# Z-Axis_Stepper_Motor_Driver.net
KiCad netlist of a schematic drawn in Altium Designer
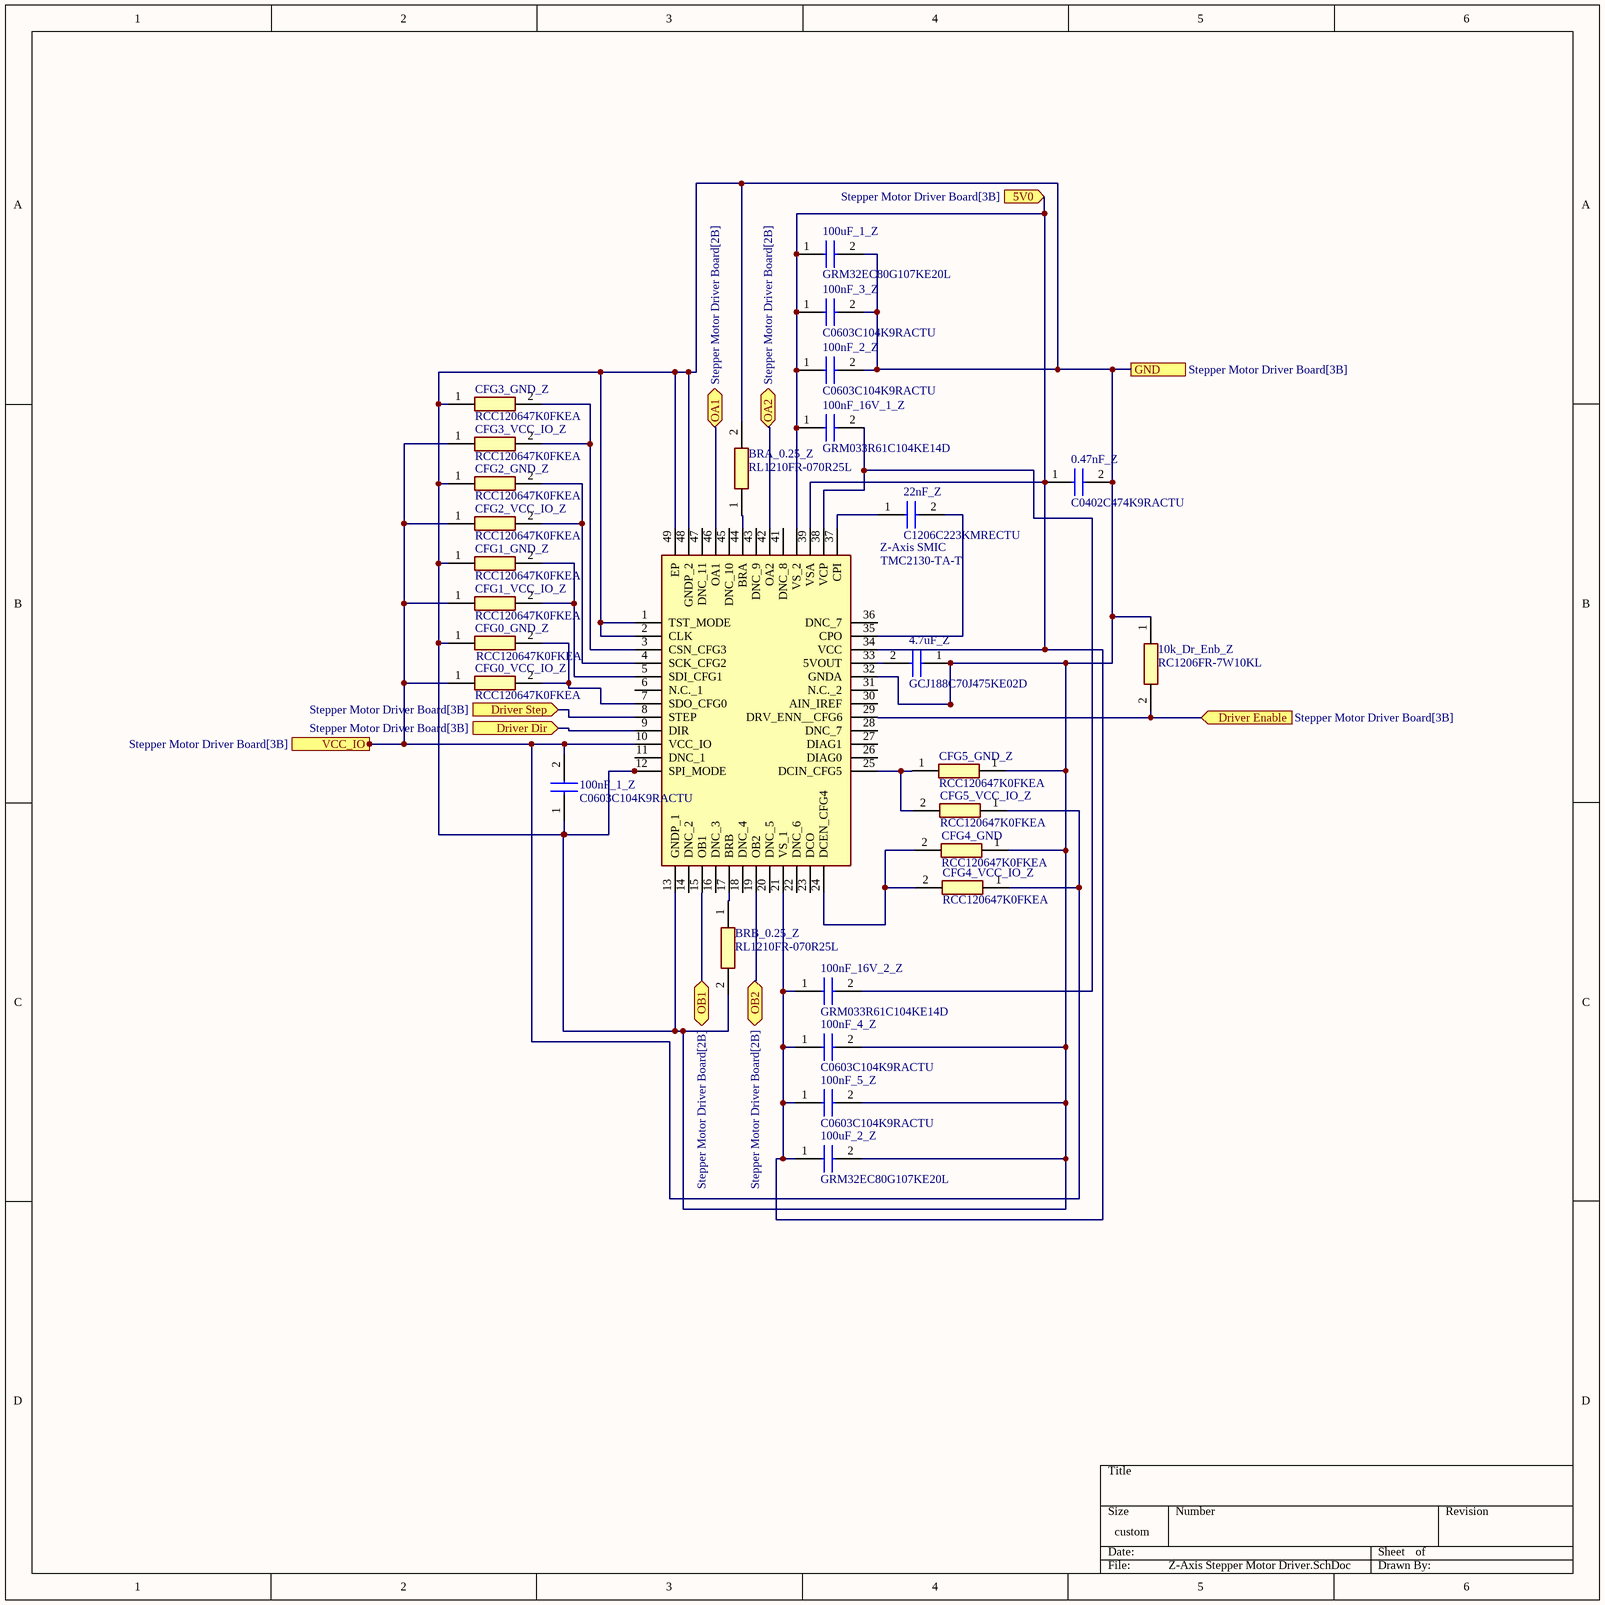
[diagram p0: Z-Axis Stepper Motor Driver.SchDoc]

(export (version "E")
  (design (tool "Eeschema 10.0.6"))
  (components
    (comp (ref "0.47nF_Z")
      (value "C0402C474K9RACTU")
      (footprint "SamacSys:CAPC1005X55N")
      (description "Capacitor")
      (fields (field (name "MOUSER PART NUMBER") "80-C0402C474K9RACTU"))
      (libsource (lib "*") (part "C0402C474K9RACTU"))
    )
    (comp (ref "4.7uF_Z")
      (value "GCJ188C70J475KE02D")
      (footprint "SamacSys:CAPC1608X100N")
      (description "Capacitor")
      (fields (field (name "MOUSER PART NUMBER") "81-GCJ188C70J475KE2D"))
      (libsource (lib "*") (part "GCJ188C70J475KE02D"))
    )
    (comp (ref "10k_Dr_Enb_Z")
      (value "RC1206FR-7W10KL")
      (footprint "SamacSys:RESC3116X65N")
      (description "Resistor")
      (libsource (lib "*") (part "RC1206FR-7W10KL"))
    )
    (comp (ref "22nF_Z")
      (value "C1206C223KMRECTU")
      (footprint "SamacSys:C1206")
      (description "Capacitor")
      (fields (field (name "MOUSER PART NUMBER") "80-C1206C223KMRECTU"))
      (libsource (lib "*") (part "C1206C223KMRECTU"))
    )
    (comp (ref "100nF_1_Z")
      (value "C0603C104K9RACTU")
      (footprint "SamacSys:C0603")
      (description "Capacitor")
      (fields (field (name "MOUSER PART NUMBER") "80-C0603C104K9R"))
      (libsource (lib "*") (part "C0603C104K9RACTU"))
    )
    (comp (ref "100nF_2_Z")
      (value "C0603C104K9RACTU")
      (footprint "SamacSys:C0603")
      (description "Capacitor")
      (fields (field (name "MOUSER PART NUMBER") "80-C0603C104K9R"))
      (libsource (lib "*") (part "C0603C104K9RACTU"))
    )
    (comp (ref "100nF_3_Z")
      (value "C0603C104K9RACTU")
      (footprint "SamacSys:C0603")
      (description "Capacitor")
      (fields (field (name "MOUSER PART NUMBER") "80-C0603C104K9R"))
      (libsource (lib "*") (part "C0603C104K9RACTU"))
    )
    (comp (ref "100nF_4_Z")
      (value "C0603C104K9RACTU")
      (footprint "SamacSys:C0603")
      (description "Capacitor")
      (fields (field (name "MOUSER PART NUMBER") "80-C0603C104K9R"))
      (libsource (lib "*") (part "C0603C104K9RACTU"))
    )
    (comp (ref "100nF_5_Z")
      (value "C0603C104K9RACTU")
      (footprint "SamacSys:C0603")
      (description "Capacitor")
      (fields (field (name "MOUSER PART NUMBER") "80-C0603C104K9R"))
      (libsource (lib "*") (part "C0603C104K9RACTU"))
    )
    (comp (ref "100nF_16V_1_Z")
      (value "GRM033R61C104KE14D")
      (footprint "SamacSys:CAPC0603X33N")
      (description "Capacitor")
      (fields (field (name "MOUSER PART NUMBER") "81-GRM033R61C104KE4D"))
      (libsource (lib "*") (part "GRM033R61C104KE14D"))
    )
    (comp (ref "100nF_16V_2_Z")
      (value "GRM033R61C104KE14D")
      (footprint "SamacSys:CAPC0603X33N")
      (description "Capacitor")
      (fields (field (name "MOUSER PART NUMBER") "81-GRM033R61C104KE4D"))
      (libsource (lib "*") (part "GRM033R61C104KE14D"))
    )
    (comp (ref "100uF_1_Z")
      (value "GRM32EC80G107KE20L")
      (footprint "SamacSys:CAPC3225X270N")
      (description "Capacitor")
      (fields (field (name "MOUSER PART NUMBER") "81-GRM32EC80G107KE0L"))
      (libsource (lib "*") (part "GRM32EC80G107KE20L"))
    )
    (comp (ref "100uF_2_Z")
      (value "GRM32EC80G107KE20L")
      (footprint "SamacSys:CAPC3225X270N")
      (description "Capacitor")
      (fields (field (name "MOUSER PART NUMBER") "81-GRM32EC80G107KE0L"))
      (libsource (lib "*") (part "GRM32EC80G107KE20L"))
    )
    (comp (ref "BRA_0.25_Z")
      (value "RL1210FR-070R25L")
      (footprint "SamacSys:RESC3126X65N")
      (description "Resistor")
      (fields (field (name "MOUSER PART NUMBER") "603-RL1210FR-070R25L"))
      (libsource (lib "") (part "RL1210FR-070R25L_1"))
    )
    (comp (ref "BRB_0.25_Z")
      (value "RL1210FR-070R25L")
      (footprint "SamacSys:RESC3126X65N")
      (description "Resistor")
      (fields (field (name "MOUSER PART NUMBER") "603-RL1210FR-070R25L"))
      (libsource (lib "*") (part "RL1210FR-070R25L"))
    )
    (comp (ref "CFG0_GND_Z")
      (value "RCC120647K0FKEA")
      (footprint "SamacSys:RCC1206_e3")
      (description "Resistor")
      (fields (field (name "MOUSER PART NUMBER") "71-RCC120647K0FKEA"))
      (libsource (lib "") (part "RCC120647K0FKEA_1"))
    )
    (comp (ref "CFG0_VCC_IO_Z")
      (value "RCC120647K0FKEA")
      (footprint "SamacSys:RCC1206_e3")
      (description "Resistor")
      (fields (field (name "MOUSER PART NUMBER") "71-RCC120647K0FKEA"))
      (libsource (lib "") (part "RCC120647K0FKEA_1"))
    )
    (comp (ref "CFG1_GND_Z")
      (value "RCC120647K0FKEA")
      (footprint "SamacSys:RCC1206_e3")
      (description "Resistor")
      (fields (field (name "MOUSER PART NUMBER") "71-RCC120647K0FKEA"))
      (libsource (lib "") (part "RCC120647K0FKEA_1"))
    )
    (comp (ref "CFG1_VCC_IO_Z")
      (value "RCC120647K0FKEA")
      (footprint "SamacSys:RCC1206_e3")
      (description "Resistor")
      (fields (field (name "MOUSER PART NUMBER") "71-RCC120647K0FKEA"))
      (libsource (lib "") (part "RCC120647K0FKEA_1"))
    )
    (comp (ref "CFG2_GND_Z")
      (value "RCC120647K0FKEA")
      (footprint "SamacSys:RCC1206_e3")
      (description "Resistor")
      (fields (field (name "MOUSER PART NUMBER") "71-RCC120647K0FKEA"))
      (libsource (lib "") (part "RCC120647K0FKEA_1"))
    )
    (comp (ref "CFG2_VCC_IO_Z")
      (value "RCC120647K0FKEA")
      (footprint "SamacSys:RCC1206_e3")
      (description "Resistor")
      (fields (field (name "MOUSER PART NUMBER") "71-RCC120647K0FKEA"))
      (libsource (lib "") (part "RCC120647K0FKEA_1"))
    )
    (comp (ref "CFG3_GND_Z")
      (value "RCC120647K0FKEA")
      (footprint "SamacSys:RCC1206_e3")
      (description "Resistor")
      (fields (field (name "MOUSER PART NUMBER") "71-RCC120647K0FKEA"))
      (libsource (lib "") (part "RCC120647K0FKEA_1"))
    )
    (comp (ref "CFG3_VCC_IO_Z")
      (value "RCC120647K0FKEA")
      (footprint "SamacSys:RCC1206_e3")
      (description "Resistor")
      (fields (field (name "MOUSER PART NUMBER") "71-RCC120647K0FKEA"))
      (libsource (lib "") (part "RCC120647K0FKEA_1"))
    )
    (comp (ref "CFG4_GND")
      (value "RCC120647K0FKEA")
      (footprint "SamacSys:RCC1206_e3")
      (description "Resistor")
      (fields (field (name "MOUSER PART NUMBER") "71-RCC120647K0FKEA"))
      (libsource (lib "*") (part "RCC120647K0FKEA"))
    )
    (comp (ref "CFG4_VCC_IO_Z")
      (value "RCC120647K0FKEA")
      (footprint "SamacSys:RCC1206_e3")
      (description "Resistor")
      (fields (field (name "MOUSER PART NUMBER") "71-RCC120647K0FKEA"))
      (libsource (lib "*") (part "RCC120647K0FKEA"))
    )
    (comp (ref "CFG5_GND_Z")
      (value "RCC120647K0FKEA")
      (footprint "SamacSys:RCC1206_e3")
      (description "Resistor")
      (fields (field (name "MOUSER PART NUMBER") "71-RCC120647K0FKEA"))
      (libsource (lib "") (part "RCC120647K0FKEA_2"))
    )
    (comp (ref "CFG5_VCC_IO_Z")
      (value "RCC120647K0FKEA")
      (footprint "SamacSys:RCC1206_e3")
      (description "Resistor")
      (fields (field (name "MOUSER PART NUMBER") "71-RCC120647K0FKEA"))
      (libsource (lib "*") (part "RCC120647K0FKEA"))
    )
    (comp (ref "Z-Axis SMIC")
      (value "TMC2130-TA-T")
      (footprint "SamacSys:QFP50P900X900X120-49N")
      (description "Integrated Circuit")
      (fields (field (name "MOUSER PART NUMBER") "700-TMC2130-TA-T"))
      (libsource (lib "*") (part "TMC2130-TA-T"))
    )
  )
  (nets
    (net (code "1") (name "/5V0") (class "Default")
      (node (ref "0.47nF_Z") (pin "1") (pinfunction "1_1") (pintype "passive"))
      (node (ref "100nF_16V_1_Z") (pin "1") (pinfunction "1_1") (pintype "passive"))
      (node (ref "100nF_16V_2_Z") (pin "1") (pinfunction "1_1") (pintype "passive"))
      (node (ref "100nF_2_Z") (pin "1") (pinfunction "1_1") (pintype "passive"))
      (node (ref "100nF_3_Z") (pin "1") (pinfunction "1_1") (pintype "passive"))
      (node (ref "100nF_4_Z") (pin "1") (pinfunction "1_1") (pintype "passive"))
      (node (ref "100nF_5_Z") (pin "1") (pinfunction "1_1") (pintype "passive"))
      (node (ref "100uF_1_Z") (pin "1") (pinfunction "1_1") (pintype "passive"))
      (node (ref "100uF_2_Z") (pin "1") (pinfunction "1_1") (pintype "passive"))
      (node (ref "Z-Axis SMIC") (pin "21") (pinfunction "VS_1_21") (pintype "passive"))
      (node (ref "Z-Axis SMIC") (pin "34") (pinfunction "VCC_34") (pintype "passive"))
      (node (ref "Z-Axis SMIC") (pin "39") (pinfunction "VSA_39") (pintype "passive"))
      (node (ref "Z-Axis SMIC") (pin "40") (pinfunction "VS_2_40") (pintype "passive"))
    )
    (net (code "2") (name "/Driver Dir") (class "Default")
      (node (ref "Z-Axis SMIC") (pin "9") (pinfunction "DIR_9") (pintype "passive"))
    )
    (net (code "3") (name "/Driver Enable") (class "Default")
      (node (ref "10k_Dr_Enb_Z") (pin "2") (pinfunction "2_2") (pintype "passive"))
      (node (ref "Z-Axis SMIC") (pin "29") (pinfunction "DRV_ENN__CFG6_29") (pintype "passive"))
    )
    (net (code "4") (name "/Driver Step") (class "Default")
      (node (ref "Z-Axis SMIC") (pin "8") (pinfunction "STEP_8") (pintype "passive"))
    )
    (net (code "5") (name "/GND") (class "Default")
      (node (ref "0.47nF_Z") (pin "2") (pinfunction "2_2") (pintype "passive"))
      (node (ref "100nF_1_Z") (pin "1") (pinfunction "1_1") (pintype "passive"))
      (node (ref "100nF_2_Z") (pin "2") (pinfunction "2_2") (pintype "passive"))
      (node (ref "100nF_3_Z") (pin "2") (pinfunction "2_2") (pintype "passive"))
      (node (ref "100nF_4_Z") (pin "2") (pinfunction "2_2") (pintype "passive"))
      (node (ref "100nF_5_Z") (pin "2") (pinfunction "2_2") (pintype "passive"))
      (node (ref "100uF_1_Z") (pin "2") (pinfunction "2_2") (pintype "passive"))
      (node (ref "100uF_2_Z") (pin "2") (pinfunction "2_2") (pintype "passive"))
      (node (ref "10k_Dr_Enb_Z") (pin "1") (pinfunction "1_1") (pintype "passive"))
      (node (ref "4.7uF_Z") (pin "1") (pinfunction "1_1") (pintype "passive"))
      (node (ref "BRA_0.25_Z") (pin "2") (pinfunction "2_2") (pintype "passive"))
      (node (ref "BRB_0.25_Z") (pin "2") (pinfunction "2_2") (pintype "passive"))
      (node (ref "CFG0_GND_Z") (pin "1") (pinfunction "1_1") (pintype "passive"))
      (node (ref "CFG1_GND_Z") (pin "1") (pinfunction "1_1") (pintype "passive"))
      (node (ref "CFG2_GND_Z") (pin "1") (pinfunction "1_1") (pintype "passive"))
      (node (ref "CFG3_GND_Z") (pin "1") (pinfunction "1_1") (pintype "passive"))
      (node (ref "CFG4_GND") (pin "1") (pinfunction "1_1") (pintype "passive"))
      (node (ref "CFG5_GND_Z") (pin "1") (pinfunction "1_1") (pintype "passive"))
      (node (ref "Z-Axis SMIC") (pin "1") (pinfunction "TST_MODE_1") (pintype "passive"))
      (node (ref "Z-Axis SMIC") (pin "12") (pinfunction "SPI_MODE_12") (pintype "passive"))
      (node (ref "Z-Axis SMIC") (pin "13") (pinfunction "GNDP_1_13") (pintype "passive"))
      (node (ref "Z-Axis SMIC") (pin "2") (pinfunction "CLK_2") (pintype "passive"))
      (node (ref "Z-Axis SMIC") (pin "32") (pinfunction "GNDA_32") (pintype "passive"))
      (node (ref "Z-Axis SMIC") (pin "48") (pinfunction "GNDP_2_48") (pintype "passive"))
      (node (ref "Z-Axis SMIC") (pin "49") (pinfunction "EP_49") (pintype "passive"))
    )
    (net (code "6") (name "/OA1") (class "Default")
      (node (ref "Z-Axis SMIC") (pin "46") (pinfunction "OA1_46") (pintype "passive"))
    )
    (net (code "7") (name "/OA2") (class "Default")
      (node (ref "Z-Axis SMIC") (pin "42") (pinfunction "OA2_42") (pintype "passive"))
    )
    (net (code "8") (name "/OB1") (class "Default")
      (node (ref "Z-Axis SMIC") (pin "15") (pinfunction "OB1_15") (pintype "passive"))
    )
    (net (code "9") (name "/OB2") (class "Default")
      (node (ref "Z-Axis SMIC") (pin "19") (pinfunction "OB2_19") (pintype "passive"))
    )
    (net (code "10") (name "/VCC_IO") (class "Default")
      (node (ref "100nF_1_Z") (pin "2") (pinfunction "2_2") (pintype "passive"))
      (node (ref "CFG0_VCC_IO_Z") (pin "1") (pinfunction "1_1") (pintype "passive"))
      (node (ref "CFG1_VCC_IO_Z") (pin "1") (pinfunction "1_1") (pintype "passive"))
      (node (ref "CFG2_VCC_IO_Z") (pin "1") (pinfunction "1_1") (pintype "passive"))
      (node (ref "CFG3_VCC_IO_Z") (pin "1") (pinfunction "1_1") (pintype "passive"))
      (node (ref "CFG4_VCC_IO_Z") (pin "1") (pinfunction "1_1") (pintype "passive"))
      (node (ref "CFG5_VCC_IO_Z") (pin "1") (pinfunction "1_1") (pintype "passive"))
      (node (ref "Z-Axis SMIC") (pin "10") (pinfunction "VCC_IO_10") (pintype "passive"))
    )
    (net (code "11") (name "Net-(Z-Axis SMIC-5VOUT)") (class "Default")
      (node (ref "4.7uF_Z") (pin "2") (pinfunction "2_2") (pintype "passive"))
      (node (ref "Z-Axis SMIC") (pin "33") (pinfunction "5VOUT_33") (pintype "passive"))
    )
    (net (code "12") (name "Net-(Z-Axis SMIC-BRA)") (class "Default")
      (node (ref "BRA_0.25_Z") (pin "1") (pinfunction "1_1") (pintype "passive"))
      (node (ref "Z-Axis SMIC") (pin "44") (pinfunction "BRA_44") (pintype "passive"))
    )
    (net (code "13") (name "Net-(Z-Axis SMIC-BRB)") (class "Default")
      (node (ref "BRB_0.25_Z") (pin "1") (pinfunction "1_1") (pintype "passive"))
      (node (ref "Z-Axis SMIC") (pin "17") (pinfunction "BRB_17") (pintype "passive"))
    )
    (net (code "14") (name "Net-(Z-Axis SMIC-CPI)") (class "Default")
      (node (ref "22nF_Z") (pin "1") (pinfunction "1_1") (pintype "passive"))
      (node (ref "Z-Axis SMIC") (pin "37") (pinfunction "CPI_37") (pintype "passive"))
    )
    (net (code "15") (name "Net-(Z-Axis SMIC-CPO)") (class "Default")
      (node (ref "22nF_Z") (pin "2") (pinfunction "2_2") (pintype "passive"))
      (node (ref "Z-Axis SMIC") (pin "35") (pinfunction "CPO_35") (pintype "passive"))
    )
    (net (code "16") (name "Net-(Z-Axis SMIC-CSN_CFG3)") (class "Default")
      (node (ref "CFG3_GND_Z") (pin "2") (pinfunction "2_2") (pintype "passive"))
      (node (ref "CFG3_VCC_IO_Z") (pin "2") (pinfunction "2_2") (pintype "passive"))
      (node (ref "Z-Axis SMIC") (pin "3") (pinfunction "CSN_CFG3_3") (pintype "passive"))
    )
    (net (code "17") (name "Net-(Z-Axis SMIC-DCEN_CFG4)") (class "Default")
      (node (ref "CFG4_GND") (pin "2") (pinfunction "2_2") (pintype "passive"))
      (node (ref "CFG4_VCC_IO_Z") (pin "2") (pinfunction "2_2") (pintype "passive"))
      (node (ref "Z-Axis SMIC") (pin "24") (pinfunction "DCEN_CFG4_24") (pintype "passive"))
    )
    (net (code "18") (name "Net-(Z-Axis SMIC-DCIN_CFG5)") (class "Default")
      (node (ref "CFG5_GND_Z") (pin "1") (pinfunction "1_1") (pintype "passive"))
      (node (ref "CFG5_VCC_IO_Z") (pin "2") (pinfunction "2_2") (pintype "passive"))
      (node (ref "Z-Axis SMIC") (pin "25") (pinfunction "DCIN_CFG5_25") (pintype "passive"))
    )
    (net (code "19") (name "Net-(Z-Axis SMIC-SCK_CFG2)") (class "Default")
      (node (ref "CFG2_GND_Z") (pin "2") (pinfunction "2_2") (pintype "passive"))
      (node (ref "CFG2_VCC_IO_Z") (pin "2") (pinfunction "2_2") (pintype "passive"))
      (node (ref "Z-Axis SMIC") (pin "4") (pinfunction "SCK_CFG2_4") (pintype "passive"))
    )
    (net (code "20") (name "Net-(Z-Axis SMIC-SDI_CFG1)") (class "Default")
      (node (ref "CFG1_GND_Z") (pin "2") (pinfunction "2_2") (pintype "passive"))
      (node (ref "CFG1_VCC_IO_Z") (pin "2") (pinfunction "2_2") (pintype "passive"))
      (node (ref "Z-Axis SMIC") (pin "5") (pinfunction "SDI_CFG1_5") (pintype "passive"))
    )
    (net (code "21") (name "Net-(Z-Axis SMIC-SDO_CFG0)") (class "Default")
      (node (ref "CFG0_GND_Z") (pin "2") (pinfunction "2_2") (pintype "passive"))
      (node (ref "CFG0_VCC_IO_Z") (pin "2") (pinfunction "2_2") (pintype "passive"))
      (node (ref "Z-Axis SMIC") (pin "7") (pinfunction "SDO_CFG0_7") (pintype "passive"))
    )
    (net (code "22") (name "Net-(Z-Axis SMIC-VCP)") (class "Default")
      (node (ref "100nF_16V_1_Z") (pin "2") (pinfunction "2_2") (pintype "passive"))
      (node (ref "100nF_16V_2_Z") (pin "2") (pinfunction "2_2") (pintype "passive"))
      (node (ref "Z-Axis SMIC") (pin "38") (pinfunction "VCP_38") (pintype "passive"))
    )
    (net (code "23") (name "unconnected-(Z-Axis SMIC-AIN_IREF-Pad30)") (class "Default")
      (node (ref "Z-Axis SMIC") (pin "30") (pinfunction "AIN_IREF_30") (pintype "passive"))
    )
    (net (code "24") (name "unconnected-(Z-Axis SMIC-DCO-Pad23)") (class "Default")
      (node (ref "Z-Axis SMIC") (pin "23") (pinfunction "DCO_23") (pintype "passive"))
    )
    (net (code "25") (name "unconnected-(Z-Axis SMIC-DIAG0-Pad26)") (class "Default")
      (node (ref "Z-Axis SMIC") (pin "26") (pinfunction "DIAG0_26") (pintype "passive"))
    )
    (net (code "26") (name "unconnected-(Z-Axis SMIC-DIAG1-Pad27)") (class "Default")
      (node (ref "Z-Axis SMIC") (pin "27") (pinfunction "DIAG1_27") (pintype "passive"))
    )
    (net (code "27") (name "unconnected-(Z-Axis SMIC-DNC_1-Pad11)") (class "Default")
      (node (ref "Z-Axis SMIC") (pin "11") (pinfunction "DNC_1_11") (pintype "passive"))
    )
    (net (code "28") (name "unconnected-(Z-Axis SMIC-DNC_2-Pad14)") (class "Default")
      (node (ref "Z-Axis SMIC") (pin "14") (pinfunction "DNC_2_14") (pintype "passive"))
    )
    (net (code "29") (name "unconnected-(Z-Axis SMIC-DNC_3-Pad16)") (class "Default")
      (node (ref "Z-Axis SMIC") (pin "16") (pinfunction "DNC_3_16") (pintype "passive"))
    )
    (net (code "30") (name "unconnected-(Z-Axis SMIC-DNC_4-Pad18)") (class "Default")
      (node (ref "Z-Axis SMIC") (pin "18") (pinfunction "DNC_4_18") (pintype "passive"))
    )
    (net (code "31") (name "unconnected-(Z-Axis SMIC-DNC_5-Pad20)") (class "Default")
      (node (ref "Z-Axis SMIC") (pin "20") (pinfunction "DNC_5_20") (pintype "passive"))
    )
    (net (code "32") (name "unconnected-(Z-Axis SMIC-DNC_6-Pad22)") (class "Default")
      (node (ref "Z-Axis SMIC") (pin "22") (pinfunction "DNC_6_22") (pintype "passive"))
    )
    (net (code "33") (name "unconnected-(Z-Axis SMIC-DNC_7-Pad28)") (class "Default")
      (node (ref "Z-Axis SMIC") (pin "28") (pinfunction "DNC_7_28") (pintype "passive"))
    )
    (net (code "34") (name "unconnected-(Z-Axis SMIC-DNC_7-Pad36)") (class "Default")
      (node (ref "Z-Axis SMIC") (pin "36") (pinfunction "DNC_7_36") (pintype "passive"))
    )
    (net (code "35") (name "unconnected-(Z-Axis SMIC-DNC_8-Pad41)") (class "Default")
      (node (ref "Z-Axis SMIC") (pin "41") (pinfunction "DNC_8_41") (pintype "passive"))
    )
    (net (code "36") (name "unconnected-(Z-Axis SMIC-DNC_9-Pad43)") (class "Default")
      (node (ref "Z-Axis SMIC") (pin "43") (pinfunction "DNC_9_43") (pintype "passive"))
    )
    (net (code "37") (name "unconnected-(Z-Axis SMIC-DNC_10-Pad45)") (class "Default")
      (node (ref "Z-Axis SMIC") (pin "45") (pinfunction "DNC_10_45") (pintype "passive"))
    )
    (net (code "38") (name "unconnected-(Z-Axis SMIC-DNC_11-Pad47)") (class "Default")
      (node (ref "Z-Axis SMIC") (pin "47") (pinfunction "DNC_11_47") (pintype "passive"))
    )
    (net (code "39") (name "unconnected-(Z-Axis SMIC-N.C._1-Pad6)") (class "Default")
      (node (ref "Z-Axis SMIC") (pin "6") (pinfunction "N.C._1_6") (pintype "passive"))
    )
    (net (code "40") (name "unconnected-(Z-Axis SMIC-N.C._2-Pad31)") (class "Default")
      (node (ref "Z-Axis SMIC") (pin "31") (pinfunction "N.C._2_31") (pintype "passive"))
    )
  )
)
